# Schematic_Analog_to_digital_Converter_Sh.net
KiCad netlist of a schematic drawn in Altium Designer
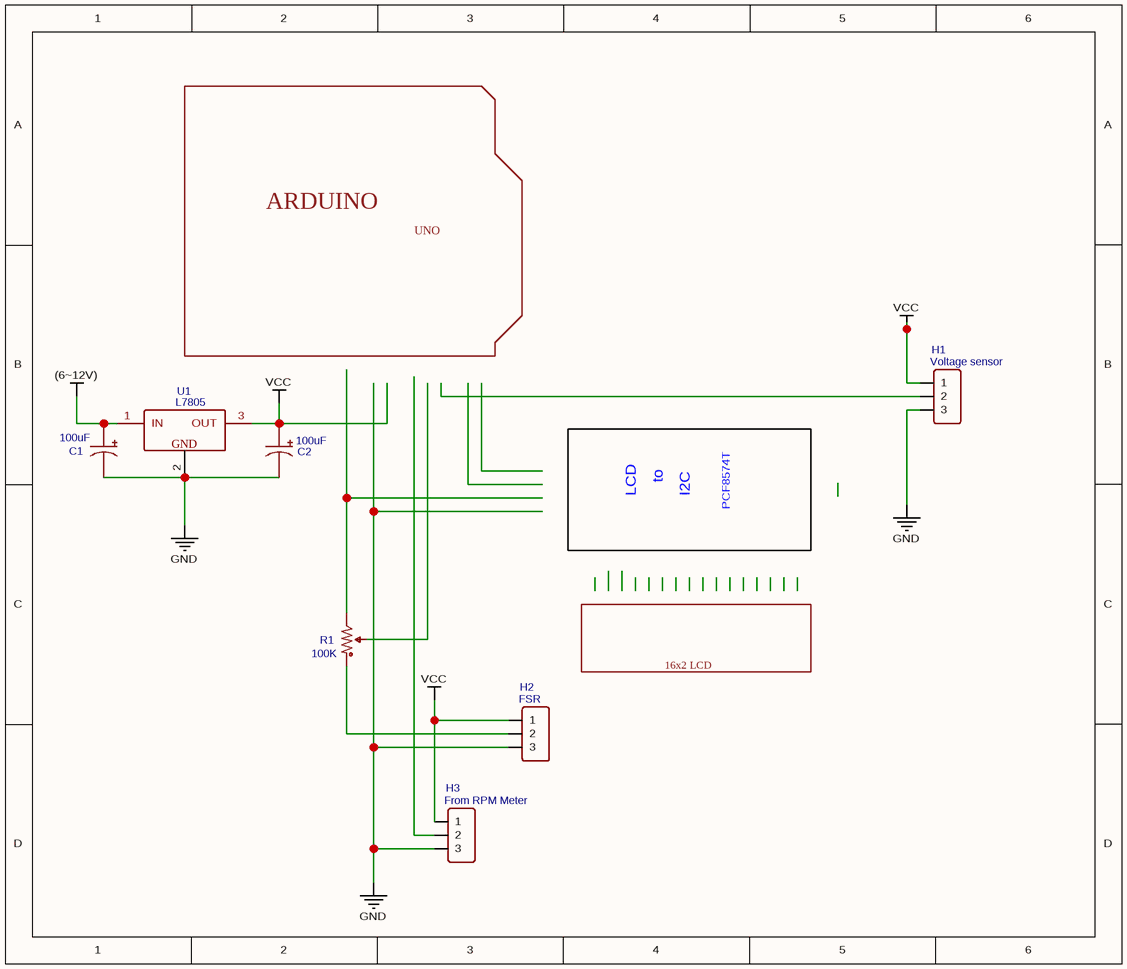
[diagram p0: Schematic_Analog to digital Converter_Sheet_.schdoc]

(export (version "E")
  (design (tool "Eeschema 10.0.6"))
  (components
    (comp (ref "C1")
      (value "100uF")
      (fields
        (field (name "BOM_SUPPLIER PART") "C442996")
        (field (name "BOM_MANUFACTURER PART") "LKMD0901H101MF")
        (field (name "CONTRIBUTOR") "LCSC")
      )
      (libsource (lib "altium-import") (part "root_1_100uF_"))
    )
    (comp (ref "C2")
      (value "100uF")
      (fields
        (field (name "BOM_SUPPLIER PART") "C442996")
        (field (name "BOM_MANUFACTURER PART") "LKMD0901H101MF")
        (field (name "CONTRIBUTOR") "LCSC")
      )
      (libsource (lib "altium-import") (part "root_1_100uF_"))
    )
    (comp (ref "H1")
      (value "Voltage sensor")
      (fields
        (field (name "BOM_MANUFACTURER PART") "Header2.54mm 1*3P")
        (field (name "BOM_SUPPLIER PART") "C49257")
      )
      (libsource (lib "altium-import") (part "root_0_Voltage sensor_"))
    )
    (comp (ref "H2")
      (value "FSR")
      (fields
        (field (name "BOM_MANUFACTURER PART") "Header2.54mm 1*3P")
        (field (name "BOM_SUPPLIER PART") "C49257")
      )
      (libsource (lib "altium-import") (part "root_0_FSR_"))
    )
    (comp (ref "H3")
      (value "From RPM Meter")
      (fields
        (field (name "BOM_MANUFACTURER PART") "Header2.54mm 1*3P")
        (field (name "BOM_SUPPLIER PART") "C49257")
      )
      (libsource (lib "altium-import") (part "root_0_From RPM Meter_"))
    )
    (comp (ref "R1")
      (value "100K")
      (fields
        (field (name "BOM_MANUFACTURER PART") "3386P-1-101LF")
        (field (name "BOM_SUPPLIER PART") "C125022")
        (field (name "CONTRIBUTOR") "EasyEDA")
      )
      (libsource (lib "altium-import") (part "root_3_100K_"))
    )
    (comp (ref "U1")
      (value "L7805")
      (fields (field (name "BOM_MANUFACTURER PART") "L7805ABV") (field (name "BOM_SUPPLIER PART") "C16807"))
      (libsource (lib "altium-import") (part "root_0_L7805_"))
    )
  )
  (nets
    (net (code "1") (name "(6~12V)") (class "Default")
      (node (ref "C1") (pin "1") (pinfunction "1_1") (pintype "passive"))
      (node (ref "U1") (pin "1") (pinfunction "IN_1") (pintype "passive"))
    )
    (net (code "2") (name "GND") (class "Default")
      (node (ref "C1") (pin "2") (pinfunction "2_2") (pintype "passive"))
      (node (ref "C2") (pin "2") (pinfunction "2_2") (pintype "passive"))
      (node (ref "H1") (pin "3") (pinfunction "3_3") (pintype "passive"))
      (node (ref "H2") (pin "3") (pinfunction "3_3") (pintype "passive"))
      (node (ref "H3") (pin "3") (pinfunction "3_3") (pintype "passive"))
      (node (ref "U1") (pin "2") (pinfunction "GND_2") (pintype "passive"))
    )
    (net (code "3") (name "Net-(H2-Pad2)") (class "Default")
      (node (ref "H2") (pin "2") (pinfunction "2_2") (pintype "passive"))
      (node (ref "R1") (pin "1") (pinfunction "1_1") (pintype "passive"))
    )
    (net (code "4") (name "VCC") (class "Default")
      (node (ref "C2") (pin "1") (pinfunction "1_1") (pintype "passive"))
      (node (ref "H1") (pin "1") (pinfunction "1_1") (pintype "passive"))
      (node (ref "H2") (pin "1") (pinfunction "1_1") (pintype "passive"))
      (node (ref "H3") (pin "1") (pinfunction "1_1") (pintype "passive"))
      (node (ref "U1") (pin "3") (pinfunction "OUT_3") (pintype "passive"))
    )
    (net (code "5") (name "unconnected-(H1-Pad2)") (class "Default")
      (node (ref "H1") (pin "2") (pinfunction "2_2") (pintype "passive"))
    )
    (net (code "6") (name "unconnected-(H3-Pad2)") (class "Default")
      (node (ref "H3") (pin "2") (pinfunction "2_2") (pintype "passive"))
    )
    (net (code "7") (name "unconnected-(R1-Pad2)") (class "Default")
      (node (ref "R1") (pin "2") (pinfunction "2_2") (pintype "passive"))
    )
    (net (code "8") (name "unconnected-(R1-Pad3)") (class "Default")
      (node (ref "R1") (pin "3") (pinfunction "3_3") (pintype "passive"))
    )
  )
)
